# power.net
KiCad netlist of a schematic drawn in Altium Designer
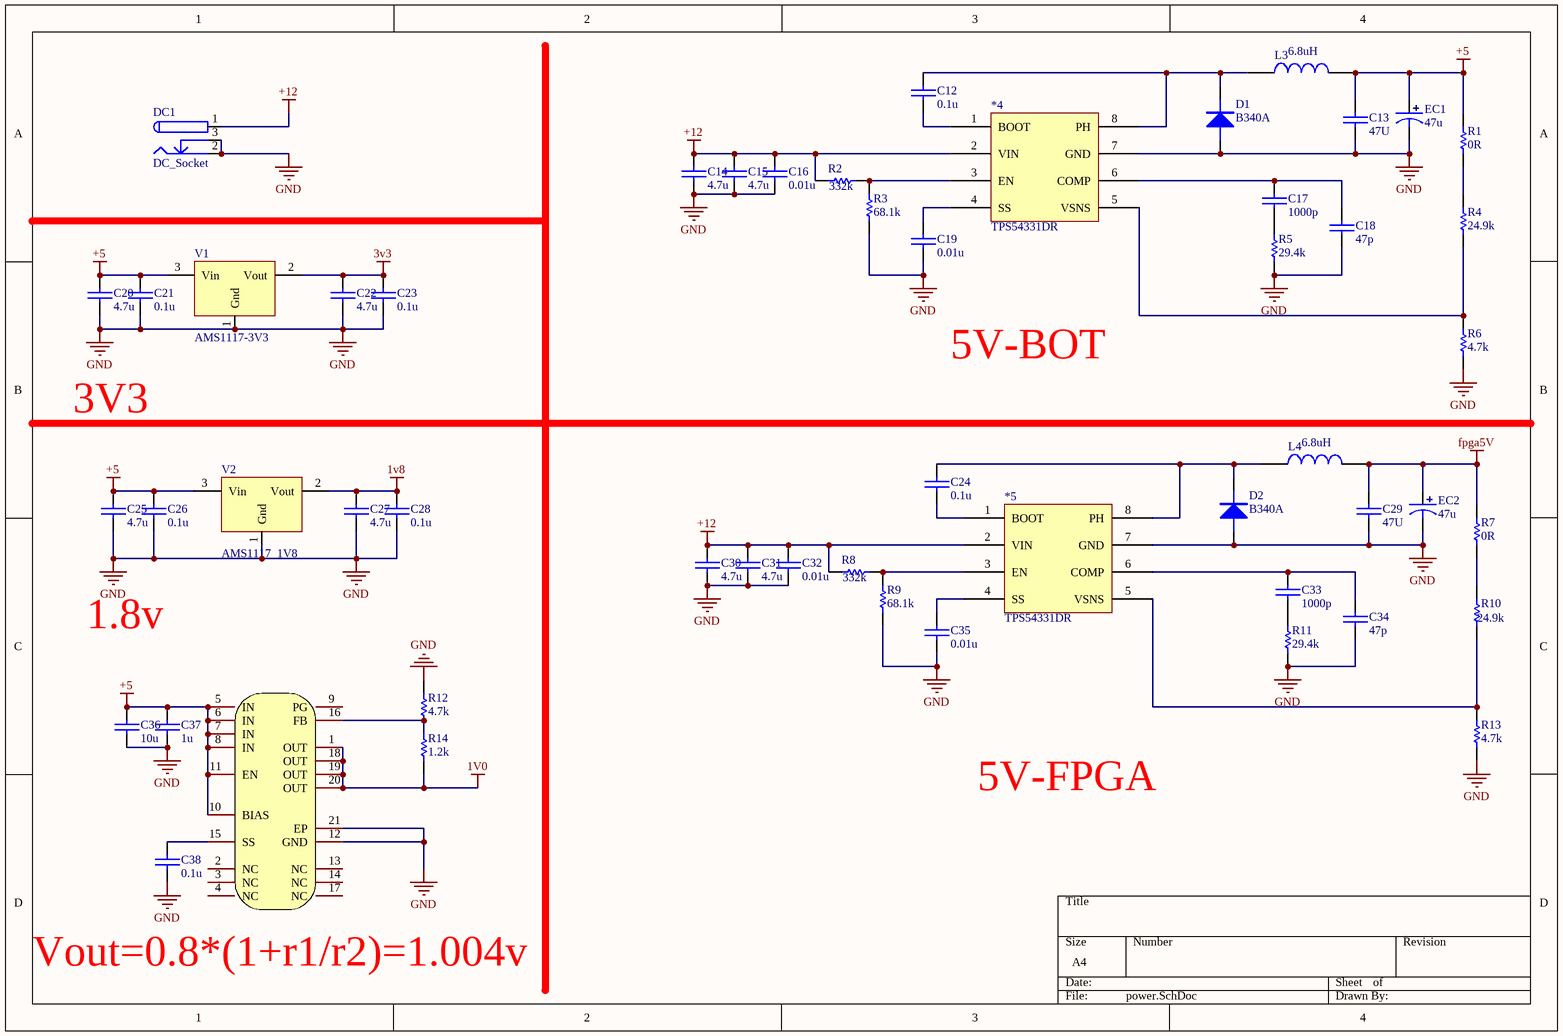
[diagram p0: power.SchDoc]

(export (version "E")
  (design (tool "Eeschema 10.0.6"))
  (components
    (comp (ref "*4")
      (value "TPS54331DR")
      (footprint "SOIC-8")
      (description "降压型DC-DC")
      (libsource (lib "0.03电源") (part "TPS54331DR"))
    )
    (comp (ref "*5")
      (value "TPS54331DR")
      (footprint "SOIC-8")
      (description "降压型DC-DC")
      (libsource (lib "0.03电源") (part "TPS54331DR"))
    )
    (comp (ref "C12")
      (value "0.1u")
      (footprint "0603C")
      (description "无极性电容")
      (libsource (lib "1.00-阻容感") (part "CAP"))
    )
    (comp (ref "C13")
      (value "47U")
      (footprint "0603C")
      (description "无极性电容")
      (libsource (lib "1.00-阻容感") (part "CAP"))
    )
    (comp (ref "C14")
      (value "4.7u")
      (footprint "0603C")
      (description "无极性电容")
      (libsource (lib "1.00-阻容感") (part "CAP"))
    )
    (comp (ref "C15")
      (value "4.7u")
      (footprint "0603C")
      (description "无极性电容")
      (libsource (lib "1.00-阻容感") (part "CAP"))
    )
    (comp (ref "C16")
      (value "0.01u")
      (footprint "0603C")
      (description "无极性电容")
      (libsource (lib "1.00-阻容感") (part "CAP"))
    )
    (comp (ref "C17")
      (value "1000p")
      (footprint "0603C")
      (description "无极性电容")
      (libsource (lib "1.00-阻容感") (part "CAP"))
    )
    (comp (ref "C18")
      (value "47p")
      (footprint "0603C")
      (description "无极性电容")
      (libsource (lib "1.00-阻容感") (part "CAP"))
    )
    (comp (ref "C19")
      (value "0.01u")
      (footprint "0603C")
      (description "无极性电容")
      (libsource (lib "1.00-阻容感") (part "CAP"))
    )
    (comp (ref "C20")
      (value "4.7u")
      (footprint "0603C")
      (description "无极性电容")
      (libsource (lib "1.00-阻容感") (part "CAP"))
    )
    (comp (ref "C21")
      (value "0.1u")
      (footprint "0603C")
      (description "无极性电容")
      (libsource (lib "1.00-阻容感") (part "CAP"))
    )
    (comp (ref "C22")
      (value "4.7u")
      (footprint "0603C")
      (description "无极性电容")
      (libsource (lib "1.00-阻容感") (part "CAP"))
    )
    (comp (ref "C23")
      (value "0.1u")
      (footprint "0603C")
      (description "无极性电容")
      (libsource (lib "1.00-阻容感") (part "CAP"))
    )
    (comp (ref "C24")
      (value "0.1u")
      (footprint "0603C")
      (description "无极性电容")
      (libsource (lib "1.00-阻容感") (part "CAP"))
    )
    (comp (ref "C25")
      (value "4.7u")
      (footprint "0603C")
      (description "无极性电容")
      (libsource (lib "1.00-阻容感") (part "CAP"))
    )
    (comp (ref "C26")
      (value "0.1u")
      (footprint "0603C")
      (description "无极性电容")
      (libsource (lib "1.00-阻容感") (part "CAP"))
    )
    (comp (ref "C27")
      (value "4.7u")
      (footprint "0603C")
      (description "无极性电容")
      (libsource (lib "1.00-阻容感") (part "CAP"))
    )
    (comp (ref "C28")
      (value "0.1u")
      (footprint "0603C")
      (description "无极性电容")
      (libsource (lib "1.00-阻容感") (part "CAP"))
    )
    (comp (ref "C29")
      (value "47U")
      (footprint "0603C")
      (description "无极性电容")
      (libsource (lib "1.00-阻容感") (part "CAP"))
    )
    (comp (ref "C30")
      (value "4.7u")
      (footprint "0603C")
      (description "无极性电容")
      (libsource (lib "1.00-阻容感") (part "CAP"))
    )
    (comp (ref "C31")
      (value "4.7u")
      (footprint "0603C")
      (description "无极性电容")
      (libsource (lib "1.00-阻容感") (part "CAP"))
    )
    (comp (ref "C32")
      (value "0.01u")
      (footprint "0603C")
      (description "无极性电容")
      (libsource (lib "1.00-阻容感") (part "CAP"))
    )
    (comp (ref "C33")
      (value "1000p")
      (footprint "0603C")
      (description "无极性电容")
      (libsource (lib "1.00-阻容感") (part "CAP"))
    )
    (comp (ref "C34")
      (value "47p")
      (footprint "0603C")
      (description "无极性电容")
      (libsource (lib "1.00-阻容感") (part "CAP"))
    )
    (comp (ref "C35")
      (value "0.01u")
      (footprint "0603C")
      (description "无极性电容")
      (libsource (lib "1.00-阻容感") (part "CAP"))
    )
    (comp (ref "C36")
      (value "10u")
      (footprint "0603C")
      (description "无极性电容")
      (libsource (lib "1.00-阻容感") (part "CAP"))
    )
    (comp (ref "C37")
      (value "1u")
      (footprint "0603C")
      (description "无极性电容")
      (libsource (lib "1.00-阻容感") (part "CAP"))
    )
    (comp (ref "C38")
      (value "0.1u")
      (footprint "0603C")
      (description "无极性电容")
      (libsource (lib "1.00-阻容感") (part "CAP"))
    )
    (comp (ref "D1")
      (value "B340A")
      (footprint "SMA/DO-214AC")
      (description "普通二极管")
      (libsource (lib "2.00-二极管") (part "DIODE"))
    )
    (comp (ref "D2")
      (value "B340A")
      (footprint "SMA/DO-214AC")
      (description "普通二极管")
      (libsource (lib "2.00-二极管") (part "DIODE"))
    )
    (comp (ref "DC1")
      (value "DC_Socket")
      (footprint "DC-005")
      (libsource (lib "9.05-电源插座") (part "DC_Socket"))
    )
    (comp (ref "EC1")
      (value "47u")
      (footprint "SMD-EC6.3X6.3X10")
      (description "贴片电解电容")
      (libsource (lib "1.00-阻容感") (part "ECAP"))
    )
    (comp (ref "EC2")
      (value "47u")
      (footprint "SMD-EC6.3X6.3X10")
      (description "贴片电解电容")
      (libsource (lib "1.00-阻容感") (part "ECAP"))
    )
    (comp (ref "L3")
      (value "6.8uH")
      (footprint "L-SMD-0630")
      (description "INDUCTOR")
      (libsource (lib "1.00-阻容感") (part "L"))
    )
    (comp (ref "L4")
      (value "6.8uH")
      (footprint "L-SMD-0630")
      (description "INDUCTOR")
      (libsource (lib "1.00-阻容感") (part "L"))
    )
    (comp (ref "R1")
      (value "0R")
      (footprint "0603R")
      (description "电阻")
      (libsource (lib "1.00-阻容感") (part "RES"))
    )
    (comp (ref "R2")
      (value "332k")
      (footprint "0603R")
      (description "电阻")
      (libsource (lib "1.00-阻容感") (part "RES"))
    )
    (comp (ref "R3")
      (value "68.1k")
      (footprint "0603R")
      (description "电阻")
      (libsource (lib "1.00-阻容感") (part "RES"))
    )
    (comp (ref "R4")
      (value "24.9k")
      (footprint "0603R")
      (description "电阻")
      (libsource (lib "1.00-阻容感") (part "RES"))
    )
    (comp (ref "R5")
      (value "29.4k")
      (footprint "0603R")
      (description "电阻")
      (libsource (lib "1.00-阻容感") (part "RES"))
    )
    (comp (ref "R6")
      (value "4.7k")
      (footprint "0603R")
      (description "电阻")
      (libsource (lib "1.00-阻容感") (part "RES"))
    )
    (comp (ref "R7")
      (value "0R")
      (footprint "0603R")
      (description "电阻")
      (libsource (lib "1.00-阻容感") (part "RES"))
    )
    (comp (ref "R8")
      (value "332k")
      (footprint "0603R")
      (description "电阻")
      (libsource (lib "1.00-阻容感") (part "RES"))
    )
    (comp (ref "R9")
      (value "68.1k")
      (footprint "0603R")
      (description "电阻")
      (libsource (lib "1.00-阻容感") (part "RES"))
    )
    (comp (ref "R10")
      (value "24.9k")
      (footprint "0603R")
      (description "电阻")
      (libsource (lib "1.00-阻容感") (part "RES"))
    )
    (comp (ref "R11")
      (value "29.4k")
      (footprint "0603R")
      (description "电阻")
      (libsource (lib "1.00-阻容感") (part "RES"))
    )
    (comp (ref "R12")
      (value "4.7k")
      (footprint "0603R")
      (description "电阻")
      (libsource (lib "1.00-阻容感") (part "RES"))
    )
    (comp (ref "R13")
      (value "4.7k")
      (footprint "0603R")
      (description "电阻")
      (libsource (lib "1.00-阻容感") (part "RES"))
    )
    (comp (ref "R14")
      (value "1.2k")
      (footprint "0603R")
      (description "电阻")
      (libsource (lib "1.00-阻容感") (part "RES"))
    )
    (comp (ref "U3")
      (value "TPS74401RGWR")
      (footprint "VQFN-20_L5.0-W5.0-P0.65-TL-EP")
      (description "单路输出 LDO、3.0A、可调节电压（0.8 至 3.3V）、快速瞬态响应、可编程软启动")
      (fields (field (name "MANUFACTURER") "TI(德州仪器)"))
      (libsource (lib "0.03电源") (part "TPS74401RGWR"))
    )
    (comp (ref "V1")
      (value "AMS1117-3V3")
      (footprint "SOT223_L")
      (description "LDO")
      (libsource (lib "0.03电源") (part "AMS1117-3V3"))
    )
    (comp (ref "V2")
      (value "AMS1117_1V8")
      (footprint "SOT223_L")
      (description "LDO")
      (libsource (lib "0.03电源") (part "AMS1117_1V8"))
    )
  )
  (nets
    (net (code "1") (name "+5") (class "Default")
      (node (ref "C13") (pin "2") (pinfunction "2_2") (pintype "passive"))
      (node (ref "C20") (pin "2") (pinfunction "2_2") (pintype "passive"))
      (node (ref "C21") (pin "2") (pinfunction "2_2") (pintype "passive"))
      (node (ref "C25") (pin "2") (pinfunction "2_2") (pintype "passive"))
      (node (ref "C26") (pin "2") (pinfunction "2_2") (pintype "passive"))
      (node (ref "C36") (pin "2") (pinfunction "2_2") (pintype "passive"))
      (node (ref "C37") (pin "2") (pinfunction "2_2") (pintype "passive"))
      (node (ref "EC1") (pin "1") (pinfunction "1_1") (pintype "passive"))
      (node (ref "L3") (pin "2") (pinfunction "2_2") (pintype "passive"))
      (node (ref "R1") (pin "2") (pinfunction "2_2") (pintype "passive"))
      (node (ref "U3") (pin "10") (pinfunction "BIAS_10") (pintype "passive"))
      (node (ref "U3") (pin "11") (pinfunction "EN_11") (pintype "passive"))
      (node (ref "U3") (pin "5") (pinfunction "IN_5") (pintype "passive"))
      (node (ref "U3") (pin "6") (pinfunction "IN_6") (pintype "passive"))
      (node (ref "U3") (pin "7") (pinfunction "IN_7") (pintype "passive"))
      (node (ref "U3") (pin "8") (pinfunction "IN_8") (pintype "passive"))
      (node (ref "V1") (pin "3") (pinfunction "Vin_3") (pintype "passive"))
      (node (ref "V2") (pin "3") (pinfunction "Vin_3") (pintype "passive"))
    )
    (net (code "2") (name "+12") (class "Default")
      (node (ref "*4") (pin "2") (pinfunction "VIN_2") (pintype "passive"))
      (node (ref "*5") (pin "2") (pinfunction "VIN_2") (pintype "passive"))
      (node (ref "C14") (pin "2") (pinfunction "2_2") (pintype "passive"))
      (node (ref "C15") (pin "2") (pinfunction "2_2") (pintype "passive"))
      (node (ref "C16") (pin "2") (pinfunction "2_2") (pintype "passive"))
      (node (ref "C30") (pin "2") (pinfunction "2_2") (pintype "passive"))
      (node (ref "C31") (pin "2") (pinfunction "2_2") (pintype "passive"))
      (node (ref "C32") (pin "2") (pinfunction "2_2") (pintype "passive"))
      (node (ref "DC1") (pin "1") (pinfunction "1_1") (pintype "power_in"))
      (node (ref "R2") (pin "2") (pinfunction "2_2") (pintype "passive"))
      (node (ref "R8") (pin "2") (pinfunction "2_2") (pintype "passive"))
    )
    (net (code "3") (name "1V0") (class "Default")
      (node (ref "R14") (pin "1") (pinfunction "1_1") (pintype "passive"))
      (node (ref "U3") (pin "1") (pinfunction "OUT_1") (pintype "passive"))
      (node (ref "U3") (pin "18") (pinfunction "OUT_18") (pintype "passive"))
      (node (ref "U3") (pin "19") (pinfunction "OUT_19") (pintype "passive"))
      (node (ref "U3") (pin "20") (pinfunction "OUT_20") (pintype "passive"))
    )
    (net (code "4") (name "1v8") (class "Default")
      (node (ref "C27") (pin "2") (pinfunction "2_2") (pintype "passive"))
      (node (ref "C28") (pin "2") (pinfunction "2_2") (pintype "passive"))
      (node (ref "V2") (pin "2") (pinfunction "Vout_2") (pintype "passive"))
    )
    (net (code "5") (name "3v3") (class "Default")
      (node (ref "C22") (pin "2") (pinfunction "2_2") (pintype "passive"))
      (node (ref "C23") (pin "2") (pinfunction "2_2") (pintype "passive"))
      (node (ref "V1") (pin "2") (pinfunction "Vout_2") (pintype "passive"))
    )
    (net (code "6") (name "GND") (class "Default")
      (node (ref "*4") (pin "7") (pinfunction "GND_7") (pintype "passive"))
      (node (ref "*5") (pin "7") (pinfunction "GND_7") (pintype "passive"))
      (node (ref "C13") (pin "1") (pinfunction "1_1") (pintype "passive"))
      (node (ref "C14") (pin "1") (pinfunction "1_1") (pintype "passive"))
      (node (ref "C15") (pin "1") (pinfunction "1_1") (pintype "passive"))
      (node (ref "C16") (pin "1") (pinfunction "1_1") (pintype "passive"))
      (node (ref "C18") (pin "1") (pinfunction "1_1") (pintype "passive"))
      (node (ref "C19") (pin "1") (pinfunction "1_1") (pintype "passive"))
      (node (ref "C20") (pin "1") (pinfunction "1_1") (pintype "passive"))
      (node (ref "C21") (pin "1") (pinfunction "1_1") (pintype "passive"))
      (node (ref "C22") (pin "1") (pinfunction "1_1") (pintype "passive"))
      (node (ref "C23") (pin "1") (pinfunction "1_1") (pintype "passive"))
      (node (ref "C25") (pin "1") (pinfunction "1_1") (pintype "passive"))
      (node (ref "C26") (pin "1") (pinfunction "1_1") (pintype "passive"))
      (node (ref "C27") (pin "1") (pinfunction "1_1") (pintype "passive"))
      (node (ref "C28") (pin "1") (pinfunction "1_1") (pintype "passive"))
      (node (ref "C29") (pin "1") (pinfunction "1_1") (pintype "passive"))
      (node (ref "C30") (pin "1") (pinfunction "1_1") (pintype "passive"))
      (node (ref "C31") (pin "1") (pinfunction "1_1") (pintype "passive"))
      (node (ref "C32") (pin "1") (pinfunction "1_1") (pintype "passive"))
      (node (ref "C34") (pin "1") (pinfunction "1_1") (pintype "passive"))
      (node (ref "C35") (pin "1") (pinfunction "1_1") (pintype "passive"))
      (node (ref "C36") (pin "1") (pinfunction "1_1") (pintype "passive"))
      (node (ref "C37") (pin "1") (pinfunction "1_1") (pintype "passive"))
      (node (ref "C38") (pin "1") (pinfunction "1_1") (pintype "passive"))
      (node (ref "D1") (pin "A") (pinfunction "A_A") (pintype "passive"))
      (node (ref "D2") (pin "A") (pinfunction "A_A") (pintype "passive"))
      (node (ref "DC1") (pin "2") (pinfunction "2_2") (pintype "power_in"))
      (node (ref "DC1") (pin "3") (pinfunction "3_3") (pintype "power_in"))
      (node (ref "EC1") (pin "2") (pinfunction "2_2") (pintype "passive"))
      (node (ref "EC2") (pin "2") (pinfunction "2_2") (pintype "passive"))
      (node (ref "R11") (pin "1") (pinfunction "1_1") (pintype "passive"))
      (node (ref "R12") (pin "2") (pinfunction "2_2") (pintype "passive"))
      (node (ref "R13") (pin "1") (pinfunction "1_1") (pintype "passive"))
      (node (ref "R3") (pin "1") (pinfunction "1_1") (pintype "passive"))
      (node (ref "R5") (pin "1") (pinfunction "1_1") (pintype "passive"))
      (node (ref "R6") (pin "1") (pinfunction "1_1") (pintype "passive"))
      (node (ref "R9") (pin "1") (pinfunction "1_1") (pintype "passive"))
      (node (ref "U3") (pin "12") (pinfunction "GND_12") (pintype "passive"))
      (node (ref "U3") (pin "21") (pinfunction "EP_21") (pintype "passive"))
      (node (ref "V1") (pin "1") (pinfunction "Gnd_1") (pintype "passive"))
      (node (ref "V2") (pin "1") (pinfunction "Gnd_1") (pintype "passive"))
    )
    (net (code "7") (name "Net-(*4-BOOT)") (class "Default")
      (node (ref "*4") (pin "1") (pinfunction "BOOT_1") (pintype "passive"))
      (node (ref "C12") (pin "1") (pinfunction "1_1") (pintype "passive"))
    )
    (net (code "8") (name "Net-(*4-COMP)") (class "Default")
      (node (ref "*4") (pin "6") (pinfunction "COMP_6") (pintype "passive"))
      (node (ref "C17") (pin "2") (pinfunction "2_2") (pintype "passive"))
      (node (ref "C18") (pin "2") (pinfunction "2_2") (pintype "passive"))
    )
    (net (code "9") (name "Net-(*4-EN)") (class "Default")
      (node (ref "*4") (pin "3") (pinfunction "EN_3") (pintype "passive"))
      (node (ref "R2") (pin "1") (pinfunction "1_1") (pintype "passive"))
      (node (ref "R3") (pin "2") (pinfunction "2_2") (pintype "passive"))
    )
    (net (code "10") (name "Net-(*4-PH)") (class "Default")
      (node (ref "*4") (pin "8") (pinfunction "PH_8") (pintype "passive"))
      (node (ref "C12") (pin "2") (pinfunction "2_2") (pintype "passive"))
      (node (ref "D1") (pin "K") (pinfunction "K_K") (pintype "passive"))
      (node (ref "L3") (pin "1") (pinfunction "1_1") (pintype "passive"))
    )
    (net (code "11") (name "Net-(*4-SS)") (class "Default")
      (node (ref "*4") (pin "4") (pinfunction "SS_4") (pintype "passive"))
      (node (ref "C19") (pin "2") (pinfunction "2_2") (pintype "passive"))
    )
    (net (code "12") (name "Net-(*4-VSNS)") (class "Default")
      (node (ref "*4") (pin "5") (pinfunction "VSNS_5") (pintype "passive"))
      (node (ref "R4") (pin "1") (pinfunction "1_1") (pintype "passive"))
      (node (ref "R6") (pin "2") (pinfunction "2_2") (pintype "passive"))
    )
    (net (code "13") (name "Net-(*5-BOOT)") (class "Default")
      (node (ref "*5") (pin "1") (pinfunction "BOOT_1") (pintype "passive"))
      (node (ref "C24") (pin "1") (pinfunction "1_1") (pintype "passive"))
    )
    (net (code "14") (name "Net-(*5-COMP)") (class "Default")
      (node (ref "*5") (pin "6") (pinfunction "COMP_6") (pintype "passive"))
      (node (ref "C33") (pin "2") (pinfunction "2_2") (pintype "passive"))
      (node (ref "C34") (pin "2") (pinfunction "2_2") (pintype "passive"))
    )
    (net (code "15") (name "Net-(*5-EN)") (class "Default")
      (node (ref "*5") (pin "3") (pinfunction "EN_3") (pintype "passive"))
      (node (ref "R8") (pin "1") (pinfunction "1_1") (pintype "passive"))
      (node (ref "R9") (pin "2") (pinfunction "2_2") (pintype "passive"))
    )
    (net (code "16") (name "Net-(*5-PH)") (class "Default")
      (node (ref "*5") (pin "8") (pinfunction "PH_8") (pintype "passive"))
      (node (ref "C24") (pin "2") (pinfunction "2_2") (pintype "passive"))
      (node (ref "D2") (pin "K") (pinfunction "K_K") (pintype "passive"))
      (node (ref "L4") (pin "1") (pinfunction "1_1") (pintype "passive"))
    )
    (net (code "17") (name "Net-(*5-SS)") (class "Default")
      (node (ref "*5") (pin "4") (pinfunction "SS_4") (pintype "passive"))
      (node (ref "C35") (pin "2") (pinfunction "2_2") (pintype "passive"))
    )
    (net (code "18") (name "Net-(*5-VSNS)") (class "Default")
      (node (ref "*5") (pin "5") (pinfunction "VSNS_5") (pintype "passive"))
      (node (ref "R10") (pin "1") (pinfunction "1_1") (pintype "passive"))
      (node (ref "R13") (pin "2") (pinfunction "2_2") (pintype "passive"))
    )
    (net (code "19") (name "Net-(C17-Pad1)") (class "Default")
      (node (ref "C17") (pin "1") (pinfunction "1_1") (pintype "passive"))
      (node (ref "R5") (pin "2") (pinfunction "2_2") (pintype "passive"))
    )
    (net (code "20") (name "Net-(C33-Pad1)") (class "Default")
      (node (ref "C33") (pin "1") (pinfunction "1_1") (pintype "passive"))
      (node (ref "R11") (pin "2") (pinfunction "2_2") (pintype "passive"))
    )
    (net (code "21") (name "Net-(R1-Pad1)") (class "Default")
      (node (ref "R1") (pin "1") (pinfunction "1_1") (pintype "passive"))
      (node (ref "R4") (pin "2") (pinfunction "2_2") (pintype "passive"))
    )
    (net (code "22") (name "Net-(R10-Pad2)") (class "Default")
      (node (ref "R10") (pin "2") (pinfunction "2_2") (pintype "passive"))
      (node (ref "R7") (pin "1") (pinfunction "1_1") (pintype "passive"))
    )
    (net (code "23") (name "Net-(U3-FB)") (class "Default")
      (node (ref "R12") (pin "1") (pinfunction "1_1") (pintype "passive"))
      (node (ref "R14") (pin "2") (pinfunction "2_2") (pintype "passive"))
      (node (ref "U3") (pin "16") (pinfunction "FB_16") (pintype "passive"))
    )
    (net (code "24") (name "Net-(U3-SS)") (class "Default")
      (node (ref "C38") (pin "2") (pinfunction "2_2") (pintype "passive"))
      (node (ref "U3") (pin "15") (pinfunction "SS_15") (pintype "passive"))
    )
    (net (code "25") (name "fpga5V") (class "Default")
      (node (ref "C29") (pin "2") (pinfunction "2_2") (pintype "passive"))
      (node (ref "EC2") (pin "1") (pinfunction "1_1") (pintype "passive"))
      (node (ref "L4") (pin "2") (pinfunction "2_2") (pintype "passive"))
      (node (ref "R7") (pin "2") (pinfunction "2_2") (pintype "passive"))
    )
    (net (code "26") (name "unconnected-(U3-NC-Pad2)") (class "Default")
      (node (ref "U3") (pin "2") (pinfunction "NC_2") (pintype "passive"))
    )
    (net (code "27") (name "unconnected-(U3-NC-Pad3)") (class "Default")
      (node (ref "U3") (pin "3") (pinfunction "NC_3") (pintype "passive"))
    )
    (net (code "28") (name "unconnected-(U3-NC-Pad4)") (class "Default")
      (node (ref "U3") (pin "4") (pinfunction "NC_4") (pintype "passive"))
    )
    (net (code "29") (name "unconnected-(U3-NC-Pad13)") (class "Default")
      (node (ref "U3") (pin "13") (pinfunction "NC_13") (pintype "passive"))
    )
    (net (code "30") (name "unconnected-(U3-NC-Pad14)") (class "Default")
      (node (ref "U3") (pin "14") (pinfunction "NC_14") (pintype "passive"))
    )
    (net (code "31") (name "unconnected-(U3-NC-Pad17)") (class "Default")
      (node (ref "U3") (pin "17") (pinfunction "NC_17") (pintype "passive"))
    )
    (net (code "32") (name "unconnected-(U3-PG-Pad9)") (class "Default")
      (node (ref "U3") (pin "9") (pinfunction "PG_9") (pintype "passive"))
    )
  )
)
